# SensorPwr.net
KiCad netlist of a schematic drawn in Altium Designer
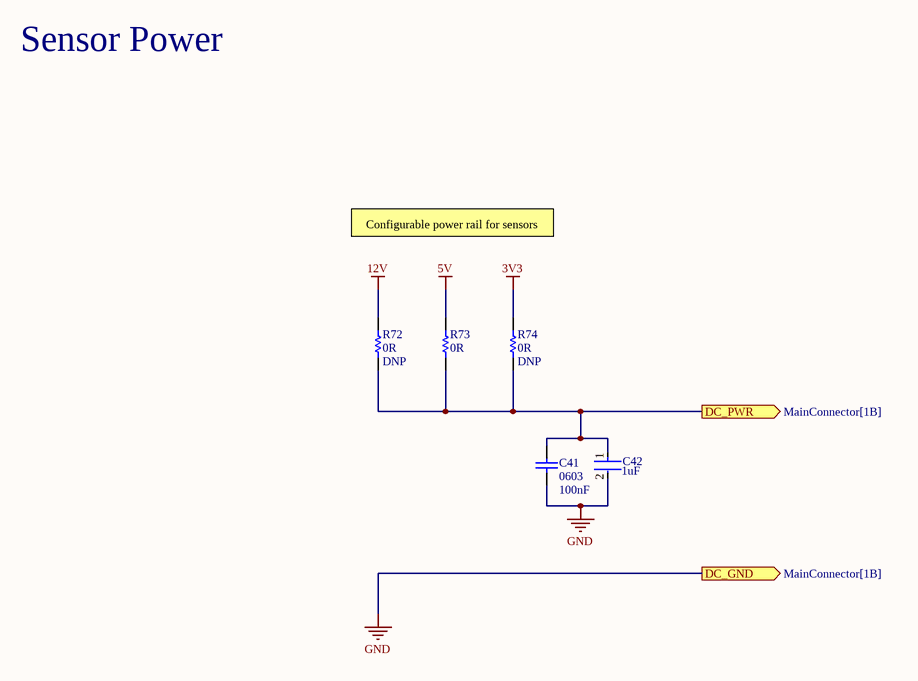
[diagram p0: SensorPwr.SchDoc]

(export (version "E")
  (design (tool "Eeschema 10.0.6"))
  (components
    (comp (ref "C41")
      (value "C0603X104K5RACTU")
      (footprint "CAPC1608X87X35NL15T15")
      (fields
        (field (name "MANUFACTURER") "Kemet")
        (field (name "CASE CODE (IMPERIAL)") "0603")
        (field (name "CAPACITANCE") "100nF")
        (field (name "TOLERANCE") "10%")
        (field (name "VOLTAGE") "50V")
      )
      (libsource (lib "Altium Content Vault") (part "CAP"))
    )
    (comp (ref "C42")
      (value "CL10A105KA8NNNC")
      (footprint "FP-CL10-IPC_C")
      (description "Cap Ceramic 1uF 25V X5R ±10% Pad SMD 0603 +85°C T/R")
      (fields
        (field (name "CAPACITANCE") "1uF")
        (field (name "VOLTAGE") "25V")
        (field (name "TOLERANCE") "10%")
      )
      (libsource (lib "Altium Content Vault") (part "b4654b650e69147ec39a6b967a45e02"))
    )
    (comp (ref "R72")
      (value "RC0805JR-100RL")
      (footprint "RESC2013X60X35LL10T20")
      (description "Chip Resistor, 0 Ohm, +/- 5%, 125 mW, -55 to 155 degC, 0805 (2012 Metric), RoHS, Tape and Reel")
      (fields
        (field (name "MANUFACTURER") "Yageo")
        (field (name "RESISTANCE") "0R")
        (field (name "DNP") "DNP")
      )
      (libsource (lib "Altium Content Vault") (part "RES-2"))
    )
    (comp (ref "R73")
      (value "RC0805JR-100RL")
      (footprint "RESC2013X60X35LL10T20")
      (description "Chip Resistor, 0 Ohm, +/- 5%, 125 mW, -55 to 155 degC, 0805 (2012 Metric), RoHS, Tape and Reel")
      (fields (field (name "MANUFACTURER") "Yageo") (field (name "RESISTANCE") "0R"))
      (libsource (lib "Altium Content Vault") (part "RES-2"))
    )
    (comp (ref "R74")
      (value "RC0805JR-100RL")
      (footprint "RESC2013X60X35LL10T20")
      (description "Chip Resistor, 0 Ohm, +/- 5%, 125 mW, -55 to 155 degC, 0805 (2012 Metric), RoHS, Tape and Reel")
      (fields
        (field (name "MANUFACTURER") "Yageo")
        (field (name "RESISTANCE") "0R")
        (field (name "DNP") "DNP")
      )
      (libsource (lib "Altium Content Vault") (part "RES-2"))
    )
  )
  (nets
    (net (code "1") (name "/DC_PWR") (class "Default")
      (node (ref "C41") (pin "1") (pinfunction "1_1") (pintype "passive"))
      (node (ref "C42") (pin "1") (pinfunction "1_1") (pintype "passive"))
      (node (ref "R72") (pin "2") (pinfunction "2_2") (pintype "passive"))
      (node (ref "R73") (pin "2") (pinfunction "2_2") (pintype "passive"))
      (node (ref "R74") (pin "2") (pinfunction "2_2") (pintype "passive"))
    )
    (net (code "2") (name "3V3") (class "Default")
      (node (ref "R74") (pin "1") (pinfunction "1_1") (pintype "passive"))
    )
    (net (code "3") (name "5V") (class "Default")
      (node (ref "R73") (pin "1") (pinfunction "1_1") (pintype "passive"))
    )
    (net (code "4") (name "12V") (class "Default")
      (node (ref "R72") (pin "1") (pinfunction "1_1") (pintype "passive"))
    )
    (net (code "5") (name "GND") (class "Default")
      (node (ref "C41") (pin "2") (pinfunction "2_2") (pintype "passive"))
      (node (ref "C42") (pin "2") (pinfunction "2_2") (pintype "passive"))
    )
  )
)
